# sensor_universal.net
KiCad netlist of a schematic drawn in EAGLE
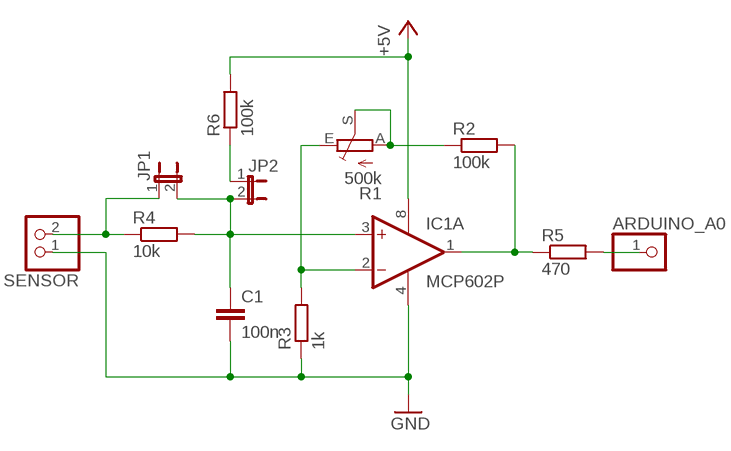
[diagram p0: schematic, sheet 1]

(export (version "E")
  (design (tool "Eeschema 10.0.6"))
  (components
    (comp (ref "ARDUINO_A0")
      (value "PINHD-1X1")
      (footprint "eagle-import:1X01")
      (libsource (lib "eagle-import") (part "PINHD-1X1"))
    )
    (comp (ref "C1")
      (value "100n")
      (footprint "eagle-import:C025-024X044")
      (libsource (lib "eagle-import") (part "C-EU025-024X044"))
    )
    (comp (ref "IC1")
      (value "MCP602P")
      (footprint "eagle-import:DIL08")
      (libsource (lib "eagle-import") (part "MCP602P"))
    )
    (comp (ref "JP1")
      (value "JP1E")
      (footprint "eagle-import:JP1")
      (libsource (lib "eagle-import") (part "JP1E"))
    )
    (comp (ref "JP2")
      (value "JP1E")
      (footprint "eagle-import:JP1")
      (libsource (lib "eagle-import") (part "JP1E"))
    )
    (comp (ref "R1")
      (value "500k")
      (footprint "eagle-import:B64Y")
      (libsource (lib "eagle-import") (part "TRIM_EU-B64Y"))
    )
    (comp (ref "R2")
      (value "100k")
      (footprint "eagle-import:0204_5")
      (libsource (lib "eagle-import") (part "R-EU_0204/5"))
    )
    (comp (ref "R3")
      (value "1k")
      (footprint "eagle-import:0204_5")
      (libsource (lib "eagle-import") (part "R-EU_0204/5"))
    )
    (comp (ref "R4")
      (value "10k")
      (footprint "eagle-import:0204_5")
      (libsource (lib "eagle-import") (part "R-EU_0204/5"))
    )
    (comp (ref "R5")
      (value "470")
      (footprint "eagle-import:0204_5")
      (libsource (lib "eagle-import") (part "R-EU_0204/5"))
    )
    (comp (ref "R6")
      (value "100k")
      (footprint "eagle-import:0204_5")
      (libsource (lib "eagle-import") (part "R-EU_0204/5"))
    )
    (comp (ref "SENSOR")
      (value "PINHD-1X2")
      (footprint "eagle-import:1X02")
      (libsource (lib "eagle-import") (part "PINHD-1X2"))
    )
  )
  (nets
    (net (code "1") (name "+5V") (class "Default")
      (node (ref "IC1") (pin "8") (pinfunction "V+_8") (pintype "power_in"))
      (node (ref "R6") (pin "2") (pinfunction "2_2") (pintype "passive"))
    )
    (net (code "2") (name "GND") (class "Default")
      (node (ref "C1") (pin "2") (pinfunction "2_2") (pintype "passive"))
      (node (ref "IC1") (pin "4") (pinfunction "V-_4") (pintype "power_in"))
      (node (ref "R3") (pin "1") (pinfunction "1_1") (pintype "passive"))
      (node (ref "SENSOR") (pin "1") (pinfunction "1_1") (pintype "passive"))
    )
    (net (code "3") (name "Net-(ARDUINO_A0-Pad1)") (class "Default")
      (node (ref "ARDUINO_A0") (pin "1") (pinfunction "1_1") (pintype "passive"))
      (node (ref "R5") (pin "2") (pinfunction "2_2") (pintype "passive"))
    )
    (net (code "4") (name "Net-(IC1A-+IN)") (class "Default")
      (node (ref "C1") (pin "1") (pinfunction "1_1") (pintype "passive"))
      (node (ref "IC1") (pin "3") (pinfunction "+IN_3") (pintype "input"))
      (node (ref "JP1") (pin "2") (pinfunction "2_2") (pintype "passive"))
      (node (ref "JP2") (pin "2") (pinfunction "2_2") (pintype "passive"))
      (node (ref "R4") (pin "2") (pinfunction "2_2") (pintype "passive"))
    )
    (net (code "5") (name "Net-(IC1A--IN)") (class "Default")
      (node (ref "IC1") (pin "2") (pinfunction "-IN_2") (pintype "input"))
      (node (ref "R1") (pin "E") (pinfunction "E_E") (pintype "passive"))
      (node (ref "R3") (pin "2") (pinfunction "2_2") (pintype "passive"))
    )
    (net (code "6") (name "Net-(IC1A-OUT)") (class "Default")
      (node (ref "IC1") (pin "1") (pinfunction "OUT_1") (pintype "output"))
      (node (ref "R2") (pin "2") (pinfunction "2_2") (pintype "passive"))
      (node (ref "R5") (pin "1") (pinfunction "1_1") (pintype "passive"))
    )
    (net (code "7") (name "Net-(JP1-Pad1)") (class "Default")
      (node (ref "JP1") (pin "1") (pinfunction "1_1") (pintype "passive"))
      (node (ref "R4") (pin "1") (pinfunction "1_1") (pintype "passive"))
      (node (ref "SENSOR") (pin "2") (pinfunction "2_2") (pintype "passive"))
    )
    (net (code "8") (name "Net-(JP2-Pad1)") (class "Default")
      (node (ref "JP2") (pin "1") (pinfunction "1_1") (pintype "passive"))
      (node (ref "R6") (pin "1") (pinfunction "1_1") (pintype "passive"))
    )
    (net (code "9") (name "Net-(R1-PadA)") (class "Default")
      (node (ref "R1") (pin "A") (pinfunction "A_A") (pintype "passive"))
      (node (ref "R1") (pin "S") (pinfunction "S_S") (pintype "passive"))
      (node (ref "R2") (pin "1") (pinfunction "1_1") (pintype "passive"))
    )
  )
)
